# Thermograph_PT100.net
KiCad netlist of a schematic drawn in Altium Designer
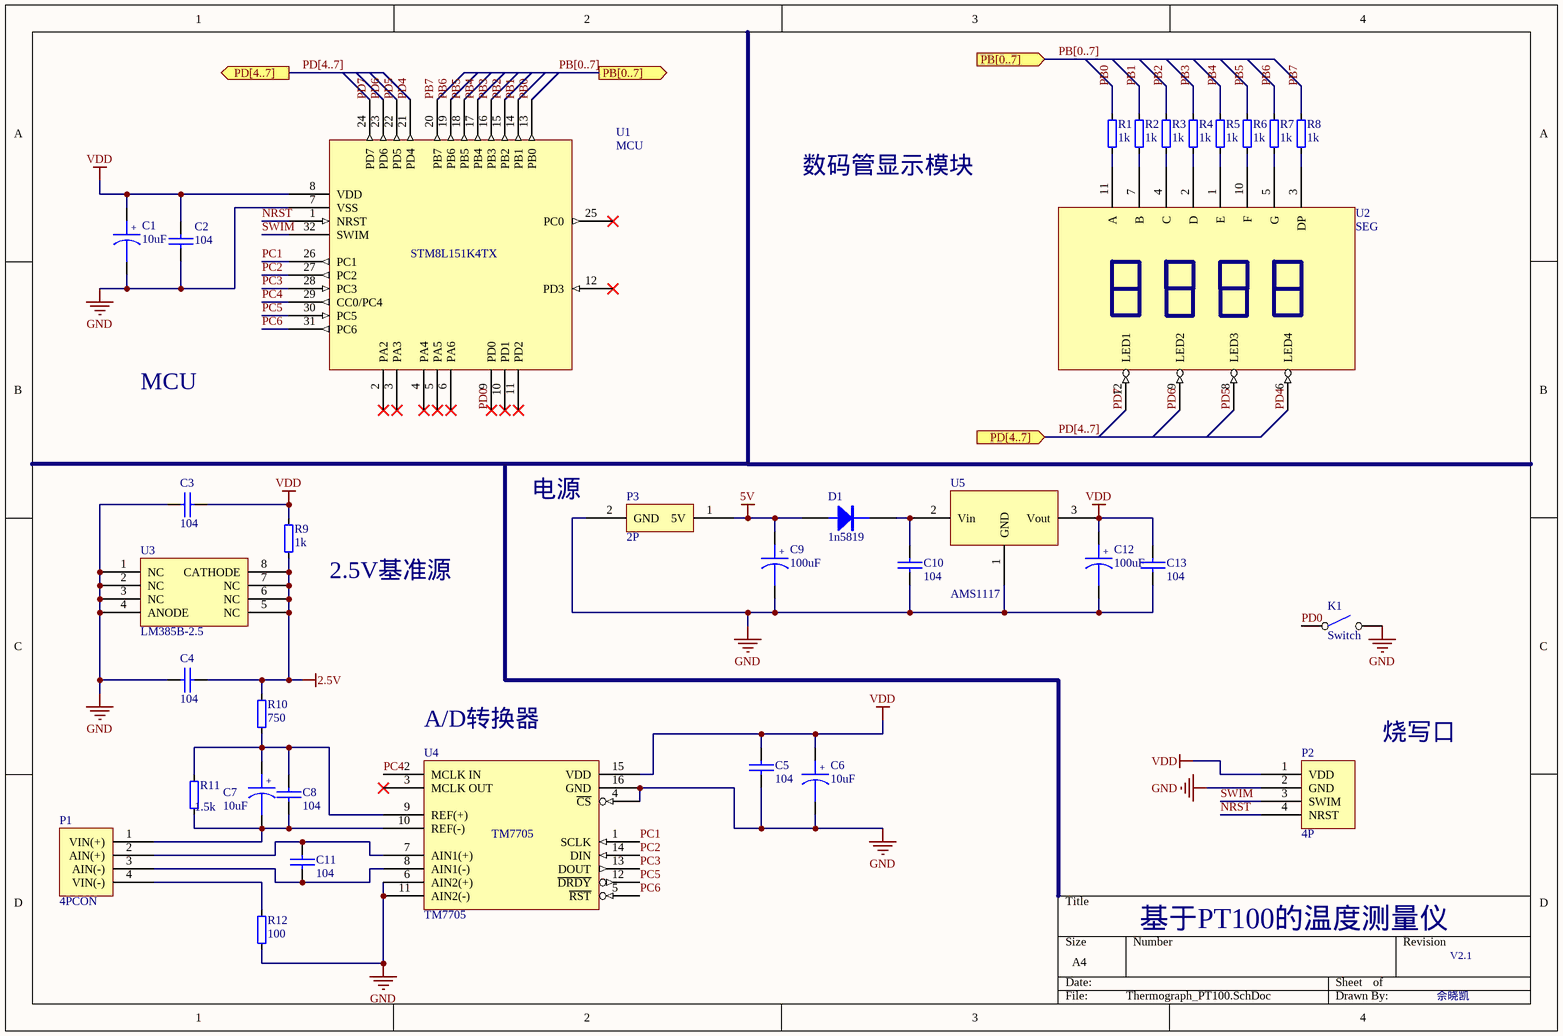
[diagram p0: Thermograph_PT100.SchDoc]

(export (version "E")
  (design (tool "Eeschema 10.0.6"))
  (components
    (comp (ref "C1")
      (value "10uF")
      (footprint "cap2")
      (description "电解电容")
      (libsource (lib "Thermograph_PT100") (part "Cap2"))
    )
    (comp (ref "C2")
      (value "104")
      (footprint "cap1")
      (description "无极性电容")
      (libsource (lib "Thermograph_PT100") (part "Cap1"))
    )
    (comp (ref "C3")
      (value "104")
      (footprint "cap1")
      (description "无极性电容")
      (libsource (lib "Thermograph_PT100") (part "Cap1"))
    )
    (comp (ref "C4")
      (value "104")
      (footprint "cap1")
      (description "无极性电容")
      (libsource (lib "Thermograph_PT100") (part "Cap1"))
    )
    (comp (ref "C5")
      (value "104")
      (footprint "cap1")
      (description "无极性电容")
      (libsource (lib "Thermograph_PT100") (part "Cap1"))
    )
    (comp (ref "C6")
      (value "10uF")
      (footprint "cap2")
      (description "电解电容")
      (libsource (lib "Thermograph_PT100") (part "Cap2"))
    )
    (comp (ref "C7")
      (value "10uF")
      (footprint "cap2")
      (description "电解电容")
      (libsource (lib "Thermograph_PT100") (part "Cap2"))
    )
    (comp (ref "C8")
      (value "104")
      (footprint "cap1")
      (description "无极性电容")
      (libsource (lib "Thermograph_PT100") (part "Cap1"))
    )
    (comp (ref "C9")
      (value "100uF")
      (footprint "cap2")
      (description "电解电容")
      (libsource (lib "Thermograph_PT100") (part "Cap2"))
    )
    (comp (ref "C10")
      (value "104")
      (footprint "cap1")
      (description "无极性电容")
      (libsource (lib "Thermograph_PT100") (part "Cap1"))
    )
    (comp (ref "C11")
      (value "104")
      (footprint "cap1")
      (description "无极性电容")
      (libsource (lib "Thermograph_PT100") (part "Cap1"))
    )
    (comp (ref "C12")
      (value "100uF")
      (footprint "cap2")
      (description "电解电容")
      (libsource (lib "Thermograph_PT100") (part "Cap2"))
    )
    (comp (ref "C13")
      (value "104")
      (footprint "cap1")
      (description "无极性电容")
      (libsource (lib "Thermograph_PT100") (part "Cap1"))
    )
    (comp (ref "D1")
      (value "1n5819")
      (footprint "1N4007")
      (description "1N4007")
      (libsource (lib "Thermograph_PT100") (part "1N4007"))
    )
    (comp (ref "K1")
      (value "Switch")
      (footprint "Switch1")
      (description "开关")
      (libsource (lib "常用元器件库") (part "Switch"))
    )
    (comp (ref "P1")
      (value "4PCON")
      (footprint "4P1")
      (description "4P端口")
      (libsource (lib "Thermograph_PT100") (part "4PCON"))
    )
    (comp (ref "P2") (value "4P") (footprint "4P2") (libsource (lib "Thermograph_PT100") (part "4P")))
    (comp (ref "P3")
      (value "2P")
      (footprint "2PXH")
      (description "5V电源")
      (libsource (lib "Thermograph_PT100") (part "2P"))
    )
    (comp (ref "R1")
      (value "1k")
      (footprint "RES")
      (description "电阻")
      (libsource (lib "Thermograph_PT100") (part "Res"))
    )
    (comp (ref "R2")
      (value "1k")
      (footprint "RES")
      (description "电阻")
      (libsource (lib "Thermograph_PT100") (part "Res"))
    )
    (comp (ref "R3")
      (value "1k")
      (footprint "RES")
      (description "电阻")
      (libsource (lib "Thermograph_PT100") (part "Res"))
    )
    (comp (ref "R4")
      (value "1k")
      (footprint "RES")
      (description "电阻")
      (libsource (lib "Thermograph_PT100") (part "Res"))
    )
    (comp (ref "R5")
      (value "1k")
      (footprint "RES")
      (description "电阻")
      (libsource (lib "Thermograph_PT100") (part "Res"))
    )
    (comp (ref "R6")
      (value "1k")
      (footprint "RES")
      (description "电阻")
      (libsource (lib "Thermograph_PT100") (part "Res"))
    )
    (comp (ref "R7")
      (value "1k")
      (footprint "RES")
      (description "电阻")
      (libsource (lib "Thermograph_PT100") (part "Res"))
    )
    (comp (ref "R8")
      (value "1k")
      (footprint "RES")
      (description "电阻")
      (libsource (lib "Thermograph_PT100") (part "Res"))
    )
    (comp (ref "R9")
      (value "1k")
      (footprint "RES")
      (description "电阻")
      (libsource (lib "Thermograph_PT100") (part "Res"))
    )
    (comp (ref "R10")
      (value "750")
      (footprint "RES")
      (description "电阻")
      (libsource (lib "Thermograph_PT100") (part "Res"))
    )
    (comp (ref "R11")
      (value "1.5k")
      (footprint "RES")
      (description "电阻")
      (libsource (lib "Thermograph_PT100") (part "Res"))
    )
    (comp (ref "R12")
      (value "100")
      (footprint "RES")
      (description "电阻")
      (libsource (lib "Thermograph_PT100") (part "Res"))
    )
    (comp (ref "U1")
      (value "MCU")
      (footprint "STM8L151K4TX")
      (description "STM8MCU")
      (libsource (lib "Thermograph_PT100") (part "STM8L151K4TX"))
    )
    (comp (ref "U2")
      (value "SEG")
      (footprint "SEG")
      (description "数码管")
      (libsource (lib "Thermograph_PT100") (part "数码管"))
    )
    (comp (ref "U3")
      (value "LM385B-2.5")
      (footprint "LM385B-2.5")
      (description "2.5V稳压芯片")
      (libsource (lib "Thermograph_PT100") (part "LM385B-2.5"))
    )
    (comp (ref "U4")
      (value "TM7705")
      (footprint "TM7705")
      (libsource (lib "Thermograph_PT100") (part "TM7705"))
    )
    (comp (ref "U5")
      (value "AMS1117")
      (footprint "AMS1117-3.3")
      (libsource (lib "Thermograph_PT100") (part "AMS1117"))
    )
  )
  (nets
    (net (code "1") (name "/NRST") (class "Default")
      (node (ref "P2") (pin "4") (pinfunction "NRST_4") (pintype "passive"))
      (node (ref "U1") (pin "1") (pinfunction "NRST_1") (pintype "input"))
    )
    (net (code "2") (name "/PB0") (class "Default")
      (node (ref "R1") (pin "2") (pinfunction "2_2") (pintype "passive"))
      (node (ref "U1") (pin "13") (pinfunction "PB0_13") (pintype "output"))
    )
    (net (code "3") (name "/PB1") (class "Default")
      (node (ref "R2") (pin "2") (pinfunction "2_2") (pintype "passive"))
      (node (ref "U1") (pin "14") (pinfunction "PB1_14") (pintype "output"))
    )
    (net (code "4") (name "/PB2") (class "Default")
      (node (ref "R3") (pin "2") (pinfunction "2_2") (pintype "passive"))
      (node (ref "U1") (pin "15") (pinfunction "PB2_15") (pintype "output"))
    )
    (net (code "5") (name "/PB3") (class "Default")
      (node (ref "R4") (pin "2") (pinfunction "2_2") (pintype "passive"))
      (node (ref "U1") (pin "16") (pinfunction "PB3_16") (pintype "output"))
    )
    (net (code "6") (name "/PB4") (class "Default")
      (node (ref "R5") (pin "2") (pinfunction "2_2") (pintype "passive"))
      (node (ref "U1") (pin "17") (pinfunction "PB4_17") (pintype "output"))
    )
    (net (code "7") (name "/PB5") (class "Default")
      (node (ref "R6") (pin "2") (pinfunction "2_2") (pintype "passive"))
      (node (ref "U1") (pin "18") (pinfunction "PB5_18") (pintype "output"))
    )
    (net (code "8") (name "/PB6") (class "Default")
      (node (ref "R7") (pin "2") (pinfunction "2_2") (pintype "passive"))
      (node (ref "U1") (pin "19") (pinfunction "PB6_19") (pintype "output"))
    )
    (net (code "9") (name "/PB7") (class "Default")
      (node (ref "R8") (pin "2") (pinfunction "2_2") (pintype "passive"))
      (node (ref "U1") (pin "20") (pinfunction "PB7_20") (pintype "output"))
    )
    (net (code "11") (name "/PC1") (class "Default")
      (node (ref "U1") (pin "26") (pinfunction "PC1_26") (pintype "output"))
      (node (ref "U4") (pin "1") (pinfunction "SCLK_1") (pintype "input"))
    )
    (net (code "12") (name "/PC2") (class "Default")
      (node (ref "U1") (pin "27") (pinfunction "PC2_27") (pintype "output"))
      (node (ref "U4") (pin "14") (pinfunction "DIN_14") (pintype "input"))
    )
    (net (code "13") (name "/PC3") (class "Default")
      (node (ref "U1") (pin "28") (pinfunction "PC3_28") (pintype "input"))
      (node (ref "U4") (pin "13") (pinfunction "DOUT_13") (pintype "output"))
    )
    (net (code "14") (name "/PC4") (class "Default")
      (node (ref "U1") (pin "29") (pinfunction "CC0/PC4_29") (pintype "output"))
      (node (ref "U4") (pin "2") (pinfunction "MCLK_IN_2") (pintype "passive"))
    )
    (net (code "15") (name "/PC5") (class "Default")
      (node (ref "U1") (pin "30") (pinfunction "PC5_30") (pintype "input"))
      (node (ref "U4") (pin "12") (pinfunction "~{DRDY}_12") (pintype "output"))
    )
    (net (code "16") (name "/PC6") (class "Default")
      (node (ref "U1") (pin "31") (pinfunction "PC6_31") (pintype "output"))
      (node (ref "U4") (pin "5") (pinfunction "~{RST}_5") (pintype "input"))
    )
    (net (code "17") (name "/PD0") (class "Default")
      (node (ref "K1") (pin "1") (pinfunction "1_1") (pintype "passive"))
      (node (ref "U1") (pin "9") (pinfunction "PD0_9") (pintype "passive"))
    )
    (net (code "18") (name "/PD4") (class "Default")
      (node (ref "U1") (pin "21") (pinfunction "PD4_21") (pintype "output"))
      (node (ref "U2") (pin "6") (pinfunction "LED4_6") (pintype "input"))
    )
    (net (code "19") (name "/PD5") (class "Default")
      (node (ref "U1") (pin "22") (pinfunction "PD5_22") (pintype "output"))
      (node (ref "U2") (pin "8") (pinfunction "LED3_8") (pintype "input"))
    )
    (net (code "20") (name "/PD6") (class "Default")
      (node (ref "U1") (pin "23") (pinfunction "PD6_23") (pintype "output"))
      (node (ref "U2") (pin "9") (pinfunction "LED2_9") (pintype "input"))
    )
    (net (code "21") (name "/PD7") (class "Default")
      (node (ref "U1") (pin "24") (pinfunction "PD7_24") (pintype "output"))
      (node (ref "U2") (pin "12") (pinfunction "LED1_12") (pintype "input"))
    )
    (net (code "23") (name "/SWIM") (class "Default")
      (node (ref "P2") (pin "3") (pinfunction "SWIM_3") (pintype "passive"))
      (node (ref "U1") (pin "32") (pinfunction "SWIM_32") (pintype "passive"))
    )
    (net (code "24") (name "2.5V") (class "Default")
      (node (ref "C4") (pin "2") (pinfunction "2_2") (pintype "passive"))
      (node (ref "R10") (pin "1") (pinfunction "1_1") (pintype "passive"))
      (node (ref "R9") (pin "1") (pinfunction "1_1") (pintype "passive"))
      (node (ref "U3") (pin "5") (pinfunction "NC_5") (pintype "passive"))
      (node (ref "U3") (pin "6") (pinfunction "NC_6") (pintype "passive"))
      (node (ref "U3") (pin "7") (pinfunction "NC_7") (pintype "passive"))
      (node (ref "U3") (pin "8") (pinfunction "CATHODE_8") (pintype "passive"))
    )
    (net (code "25") (name "5V") (class "Default")
      (node (ref "C9") (pin "A") (pinfunction "A_A") (pintype "passive"))
      (node (ref "D1") (pin "A") (pinfunction "A_A") (pintype "passive"))
      (node (ref "P3") (pin "1") (pinfunction "5V_1") (pintype "passive"))
    )
    (net (code "26") (name "GND") (class "Default")
      (node (ref "C1") (pin "K") (pinfunction "K_K") (pintype "passive"))
      (node (ref "C10") (pin "1") (pinfunction "1_1") (pintype "passive"))
      (node (ref "C12") (pin "K") (pinfunction "K_K") (pintype "passive"))
      (node (ref "C13") (pin "1") (pinfunction "1_1") (pintype "passive"))
      (node (ref "C2") (pin "1") (pinfunction "1_1") (pintype "passive"))
      (node (ref "C3") (pin "1") (pinfunction "1_1") (pintype "passive"))
      (node (ref "C4") (pin "1") (pinfunction "1_1") (pintype "passive"))
      (node (ref "C5") (pin "1") (pinfunction "1_1") (pintype "passive"))
      (node (ref "C6") (pin "K") (pinfunction "K_K") (pintype "passive"))
      (node (ref "C9") (pin "K") (pinfunction "K_K") (pintype "passive"))
      (node (ref "K1") (pin "2") (pinfunction "2_2") (pintype "passive"))
      (node (ref "P2") (pin "2") (pinfunction "GND_2") (pintype "passive"))
      (node (ref "P3") (pin "2") (pinfunction "GND_2") (pintype "passive"))
      (node (ref "R12") (pin "2") (pinfunction "2_2") (pintype "passive"))
      (node (ref "U1") (pin "7") (pinfunction "VSS_7") (pintype "power_in"))
      (node (ref "U3") (pin "1") (pinfunction "NC_1") (pintype "passive"))
      (node (ref "U3") (pin "2") (pinfunction "NC_2") (pintype "passive"))
      (node (ref "U3") (pin "3") (pinfunction "NC_3") (pintype "passive"))
      (node (ref "U3") (pin "4") (pinfunction "ANODE_4") (pintype "passive"))
      (node (ref "U4") (pin "11") (pinfunction "AIN2(-)_11") (pintype "passive"))
      (node (ref "U4") (pin "16") (pinfunction "GND_16") (pintype "power_in"))
      (node (ref "U4") (pin "4") (pinfunction "~{CS}_4") (pintype "input"))
      (node (ref "U4") (pin "6") (pinfunction "AIN2(+)_6") (pintype "passive"))
      (node (ref "U5") (pin "1") (pinfunction "GND_1") (pintype "passive"))
    )
    (net (code "27") (name "Net-(P1-AIN(+))") (class "Default")
      (node (ref "C11") (pin "2") (pinfunction "2_2") (pintype "passive"))
      (node (ref "P1") (pin "2") (pinfunction "AIN(+)_2") (pintype "passive"))
      (node (ref "U4") (pin "7") (pinfunction "AIN1(+)_7") (pintype "passive"))
    )
    (net (code "28") (name "Net-(P1-AIN(-))") (class "Default")
      (node (ref "C11") (pin "1") (pinfunction "1_1") (pintype "passive"))
      (node (ref "P1") (pin "3") (pinfunction "AIN(-)_3") (pintype "passive"))
      (node (ref "U4") (pin "8") (pinfunction "AIN1(-)_8") (pintype "passive"))
    )
    (net (code "29") (name "Net-(P1-VIN(+))") (class "Default")
      (node (ref "C7") (pin "K") (pinfunction "K_K") (pintype "passive"))
      (node (ref "C8") (pin "1") (pinfunction "1_1") (pintype "passive"))
      (node (ref "P1") (pin "1") (pinfunction "VIN(+)_1") (pintype "passive"))
      (node (ref "R11") (pin "1") (pinfunction "1_1") (pintype "passive"))
      (node (ref "U4") (pin "10") (pinfunction "REF(-)_10") (pintype "passive"))
    )
    (net (code "30") (name "Net-(P1-VIN(-))") (class "Default")
      (node (ref "P1") (pin "4") (pinfunction "VIN(-)_4") (pintype "passive"))
      (node (ref "R12") (pin "1") (pinfunction "1_1") (pintype "passive"))
    )
    (net (code "31") (name "Net-(U2-A)") (class "Default")
      (node (ref "R1") (pin "1") (pinfunction "1_1") (pintype "passive"))
      (node (ref "U2") (pin "11") (pinfunction "A_11") (pintype "passive"))
    )
    (net (code "32") (name "Net-(U2-B)") (class "Default")
      (node (ref "R2") (pin "1") (pinfunction "1_1") (pintype "passive"))
      (node (ref "U2") (pin "7") (pinfunction "B_7") (pintype "passive"))
    )
    (net (code "33") (name "Net-(U2-C)") (class "Default")
      (node (ref "R3") (pin "1") (pinfunction "1_1") (pintype "passive"))
      (node (ref "U2") (pin "4") (pinfunction "C_4") (pintype "passive"))
    )
    (net (code "34") (name "Net-(U2-D)") (class "Default")
      (node (ref "R4") (pin "1") (pinfunction "1_1") (pintype "passive"))
      (node (ref "U2") (pin "2") (pinfunction "D_2") (pintype "passive"))
    )
    (net (code "35") (name "Net-(U2-DP)") (class "Default")
      (node (ref "R8") (pin "1") (pinfunction "1_1") (pintype "passive"))
      (node (ref "U2") (pin "3") (pinfunction "DP_3") (pintype "passive"))
    )
    (net (code "36") (name "Net-(U2-E)") (class "Default")
      (node (ref "R5") (pin "1") (pinfunction "1_1") (pintype "passive"))
      (node (ref "U2") (pin "1") (pinfunction "E_1") (pintype "passive"))
    )
    (net (code "37") (name "Net-(U2-F)") (class "Default")
      (node (ref "R6") (pin "1") (pinfunction "1_1") (pintype "passive"))
      (node (ref "U2") (pin "10") (pinfunction "F_10") (pintype "passive"))
    )
    (net (code "38") (name "Net-(U2-G)") (class "Default")
      (node (ref "R7") (pin "1") (pinfunction "1_1") (pintype "passive"))
      (node (ref "U2") (pin "5") (pinfunction "G_5") (pintype "passive"))
    )
    (net (code "39") (name "Net-(U4-REF(+))") (class "Default")
      (node (ref "C7") (pin "A") (pinfunction "A_A") (pintype "passive"))
      (node (ref "C8") (pin "2") (pinfunction "2_2") (pintype "passive"))
      (node (ref "R10") (pin "2") (pinfunction "2_2") (pintype "passive"))
      (node (ref "R11") (pin "2") (pinfunction "2_2") (pintype "passive"))
      (node (ref "U4") (pin "9") (pinfunction "REF(+)_9") (pintype "passive"))
    )
    (net (code "40") (name "Net-(U5-Vin)") (class "Default")
      (node (ref "C10") (pin "2") (pinfunction "2_2") (pintype "passive"))
      (node (ref "D1") (pin "K") (pinfunction "K_K") (pintype "passive"))
      (node (ref "U5") (pin "2") (pinfunction "Vin_2") (pintype "power_in"))
    )
    (net (code "41") (name "VDD") (class "Default")
      (node (ref "C1") (pin "A") (pinfunction "A_A") (pintype "passive"))
      (node (ref "C12") (pin "A") (pinfunction "A_A") (pintype "passive"))
      (node (ref "C13") (pin "2") (pinfunction "2_2") (pintype "passive"))
      (node (ref "C2") (pin "2") (pinfunction "2_2") (pintype "passive"))
      (node (ref "C3") (pin "2") (pinfunction "2_2") (pintype "passive"))
      (node (ref "C5") (pin "2") (pinfunction "2_2") (pintype "passive"))
      (node (ref "C6") (pin "A") (pinfunction "A_A") (pintype "passive"))
      (node (ref "P2") (pin "1") (pinfunction "VDD_1") (pintype "passive"))
      (node (ref "R9") (pin "2") (pinfunction "2_2") (pintype "passive"))
      (node (ref "U1") (pin "8") (pinfunction "VDD_8") (pintype "power_in"))
      (node (ref "U4") (pin "15") (pinfunction "VDD_15") (pintype "power_in"))
      (node (ref "U5") (pin "3") (pinfunction "Vout_3") (pintype "passive"))
    )
    (net (code "42") (name "unconnected-(U1-PA2-Pad2)") (class "Default")
      (node (ref "U1") (pin "2") (pinfunction "PA2_2") (pintype "passive+no_connect"))
    )
    (net (code "43") (name "unconnected-(U1-PA3-Pad3)") (class "Default")
      (node (ref "U1") (pin "3") (pinfunction "PA3_3") (pintype "passive+no_connect"))
    )
    (net (code "44") (name "unconnected-(U1-PA4-Pad4)") (class "Default")
      (node (ref "U1") (pin "4") (pinfunction "PA4_4") (pintype "passive+no_connect"))
    )
    (net (code "45") (name "unconnected-(U1-PA5-Pad5)") (class "Default")
      (node (ref "U1") (pin "5") (pinfunction "PA5_5") (pintype "passive+no_connect"))
    )
    (net (code "46") (name "unconnected-(U1-PA6-Pad6)") (class "Default")
      (node (ref "U1") (pin "6") (pinfunction "PA6_6") (pintype "passive+no_connect"))
    )
    (net (code "47") (name "unconnected-(U1-PC0-Pad25)") (class "Default")
      (node (ref "U1") (pin "25") (pinfunction "PC0_25") (pintype "output+no_connect"))
    )
    (net (code "48") (name "unconnected-(U1-PD1-Pad10)") (class "Default")
      (node (ref "U1") (pin "10") (pinfunction "PD1_10") (pintype "passive+no_connect"))
    )
    (net (code "49") (name "unconnected-(U1-PD2-Pad11)") (class "Default")
      (node (ref "U1") (pin "11") (pinfunction "PD2_11") (pintype "passive+no_connect"))
    )
    (net (code "50") (name "unconnected-(U1-PD3-Pad12)") (class "Default")
      (node (ref "U1") (pin "12") (pinfunction "PD3_12") (pintype "input+no_connect"))
    )
    (net (code "51") (name "unconnected-(U4-MCLK_OUT-Pad3)") (class "Default")
      (node (ref "U4") (pin "3") (pinfunction "MCLK_OUT_3") (pintype "passive+no_connect"))
    )
  )
)
